# 10ms_Debouncer.net
KiCad netlist of a schematic drawn in Altium Designer
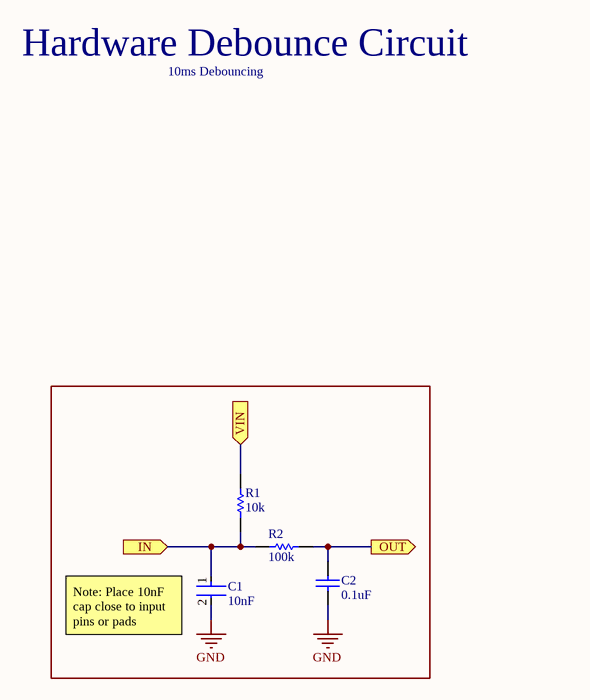
[diagram p0: 10ms Debouncer.SchDoc]

(export (version "E")
  (design (tool "Eeschema 10.0.6"))
  (components
    (comp (ref "C1")
      (value "10nF")
      (footprint "FP-CL21-IPC_A")
      (description "CL21 Series 0805 10nF 100V ±10% Tolerance X7R Multilayer Ceramic Chip Capacitor")
      (fields (field (name "VOLTAGE") "100V") (field (name "TOLERANCE") "10%"))
      (libsource (lib "Altium Content Vault") (part "b4654b650e69147ec39a6b967a45e02"))
    )
    (comp (ref "C2")
      (value "0.1uF")
      (footprint "CAPC2013X95X45ML10T25")
      (description "Chip Capacitor, 0.1 uF, +/- 10%, 50 V, 0805 (2012 Metric), RoHS, Tape and Reel")
      (fields
        (field (name "MANUFACTURER") "Samsung Electro-Mechanics")
        (field (name "MANUFACTURER PART NUMBER") "CL21B104KBCNNNC")
      )
      (libsource (lib "Altium Content Vault") (part "CAP-NP-2"))
    )
    (comp (ref "R1")
      (value "10k")
      (footprint "RESC2013X70X40LL20T20")
      (fields
        (field (name "PART NUMBER") "ERJ-6GEYJ103V")
        (field (name "MANUFACTURER") "Panasonic")
        (field (name "TOLERANCE") "5%")
      )
      (libsource (lib "Altium Content Vault") (part "RES"))
    )
    (comp (ref "R2")
      (value "100k")
      (footprint "RESC2013X70X40ML20T20")
      (fields
        (field (name "PART NUMBER") "ERJ-6ENF1003V")
        (field (name "MANUFACTURER") "Panasonic")
        (field (name "TOLERANCE") "1%")
      )
      (libsource (lib "Altium Content Vault") (part "RES"))
    )
  )
  (nets
    (net (code "1") (name "/IN") (class "Default")
      (node (ref "C1") (pin "1") (pinfunction "1_1") (pintype "passive"))
      (node (ref "R1") (pin "1") (pinfunction "1_1") (pintype "passive"))
      (node (ref "R2") (pin "1") (pinfunction "1_1") (pintype "passive"))
    )
    (net (code "2") (name "/OUT") (class "Default")
      (node (ref "C2") (pin "1") (pinfunction "1_1") (pintype "passive"))
      (node (ref "R2") (pin "2") (pinfunction "2_2") (pintype "passive"))
    )
    (net (code "3") (name "/VIN") (class "Default")
      (node (ref "R1") (pin "2") (pinfunction "2_2") (pintype "passive"))
    )
    (net (code "4") (name "GND") (class "Default")
      (node (ref "C1") (pin "2") (pinfunction "2_2") (pintype "passive"))
      (node (ref "C2") (pin "2") (pinfunction "2_2") (pintype "passive"))
    )
  )
)
